# Deserializer.net
KiCad netlist of a schematic drawn in Altium Designer
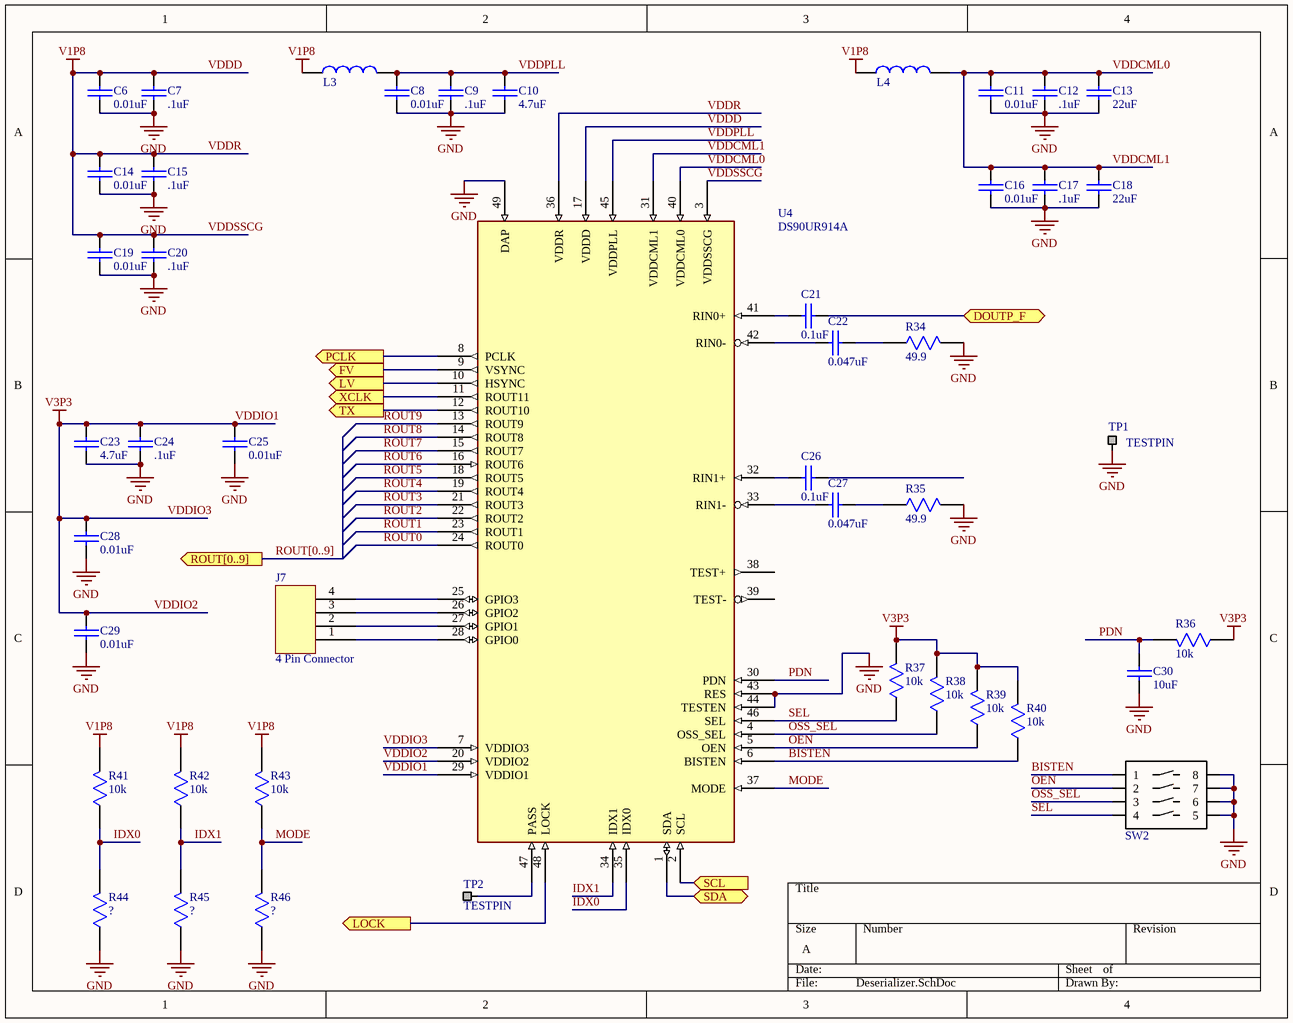
[diagram p0: Deserializer.SchDoc]

(export (version "E")
  (design (tool "Eeschema 10.0.6"))
  (components
    (comp (ref "C6")
      (value "0.01uF")
      (footprint "SMD Capacitor 0603")
      (libsource (lib "DA_Component_Library") (part "Capacitor"))
    )
    (comp (ref "C7")
      (value ".1uF")
      (footprint "SMD Capacitor 0603")
      (libsource (lib "DA_Component_Library") (part "Capacitor"))
    )
    (comp (ref "C8")
      (value "0.01uF")
      (footprint "SMD Capacitor 0603")
      (libsource (lib "DA_Component_Library") (part "Capacitor"))
    )
    (comp (ref "C9")
      (value ".1uF")
      (footprint "SMD Capacitor 0603")
      (libsource (lib "DA_Component_Library") (part "Capacitor"))
    )
    (comp (ref "C10")
      (value "4.7uF")
      (footprint "SMD Capacitor 0603")
      (libsource (lib "DA_Component_Library") (part "Capacitor"))
    )
    (comp (ref "C11")
      (value "0.01uF")
      (footprint "SMD Capacitor 0603")
      (libsource (lib "DA_Component_Library") (part "Capacitor"))
    )
    (comp (ref "C12")
      (value ".1uF")
      (footprint "SMD Capacitor 0603")
      (libsource (lib "DA_Component_Library") (part "Capacitor"))
    )
    (comp (ref "C13")
      (value "22uF")
      (footprint "SMD Capacitor 0603")
      (libsource (lib "DA_Component_Library") (part "Capacitor"))
    )
    (comp (ref "C14")
      (value "0.01uF")
      (footprint "SMD Capacitor 0603")
      (libsource (lib "DA_Component_Library") (part "Capacitor"))
    )
    (comp (ref "C15")
      (value ".1uF")
      (footprint "SMD Capacitor 0603")
      (libsource (lib "DA_Component_Library") (part "Capacitor"))
    )
    (comp (ref "C16")
      (value "0.01uF")
      (footprint "SMD Capacitor 0603")
      (libsource (lib "DA_Component_Library") (part "Capacitor"))
    )
    (comp (ref "C17")
      (value ".1uF")
      (footprint "SMD Capacitor 0603")
      (libsource (lib "DA_Component_Library") (part "Capacitor"))
    )
    (comp (ref "C18")
      (value "22uF")
      (footprint "SMD Capacitor 0603")
      (libsource (lib "DA_Component_Library") (part "Capacitor"))
    )
    (comp (ref "C19")
      (value "0.01uF")
      (footprint "SMD Capacitor 0603")
      (libsource (lib "DA_Component_Library") (part "Capacitor"))
    )
    (comp (ref "C20")
      (value ".1uF")
      (footprint "SMD Capacitor 0603")
      (libsource (lib "DA_Component_Library") (part "Capacitor"))
    )
    (comp (ref "C21")
      (value "0.1uF")
      (footprint "SMD CAP 0402")
      (libsource (lib "DA_Component_Library") (part "Capacitor"))
    )
    (comp (ref "C22")
      (value "0.047uF")
      (footprint "SMD CAP 0402")
      (libsource (lib "DA_Component_Library") (part "Capacitor"))
    )
    (comp (ref "C23")
      (value "4.7uF")
      (footprint "SMD Capacitor 0603")
      (libsource (lib "DA_Component_Library") (part "Capacitor"))
    )
    (comp (ref "C24")
      (value ".1uF")
      (footprint "SMD Capacitor 0603")
      (libsource (lib "DA_Component_Library") (part "Capacitor"))
    )
    (comp (ref "C25")
      (value "0.01uF")
      (footprint "SMD Capacitor 0603")
      (libsource (lib "DA_Component_Library") (part "Capacitor"))
    )
    (comp (ref "C26")
      (value "0.1uF")
      (footprint "SMD CAP 0402")
      (libsource (lib "DA_Component_Library") (part "Capacitor"))
    )
    (comp (ref "C27")
      (value "0.047uF")
      (footprint "SMD CAP 0402")
      (libsource (lib "DA_Component_Library") (part "Capacitor"))
    )
    (comp (ref "C28")
      (value "0.01uF")
      (footprint "SMD Capacitor 0603")
      (libsource (lib "DA_Component_Library") (part "Capacitor"))
    )
    (comp (ref "C29")
      (value "0.01uF")
      (footprint "SMD Capacitor 0603")
      (libsource (lib "DA_Component_Library") (part "Capacitor"))
    )
    (comp (ref "C30")
      (value "10uF")
      (footprint "SMD Capacitor 0603")
      (libsource (lib "DA_Component_Library") (part "Capacitor"))
    )
    (comp (ref "J7")
      (value "4 Pin Connector")
      (footprint "4Pin Verital 0.1\"")
      (libsource (lib "DA_Component_Library") (part "4 Pin Connector"))
    )
    (comp (ref "L3")
      (value "Ferrite Bead")
      (footprint "BLM18KG601SN1D")
      (libsource (lib "DA_Component_Library") (part "Ferrite Bead"))
    )
    (comp (ref "L4")
      (value "Ferrite Bead")
      (footprint "BLM18KG601SN1D")
      (libsource (lib "DA_Component_Library") (part "Ferrite Bead"))
    )
    (comp (ref "R34")
      (value "49.9")
      (footprint "SMD RES 0402")
      (libsource (lib "DA_Component_Library") (part "Resistor"))
    )
    (comp (ref "R35")
      (value "49.9")
      (footprint "SMD RES 0402")
      (libsource (lib "DA_Component_Library") (part "Resistor"))
    )
    (comp (ref "R36")
      (value "10k")
      (footprint "SMD Resistor 0603")
      (libsource (lib "DA_Component_Library") (part "Resistor"))
    )
    (comp (ref "R37")
      (value "10k")
      (footprint "SMD Resistor 0603")
      (libsource (lib "DA_Component_Library") (part "Resistor"))
    )
    (comp (ref "R38")
      (value "10k")
      (footprint "SMD Resistor 0603")
      (libsource (lib "DA_Component_Library") (part "Resistor"))
    )
    (comp (ref "R39")
      (value "10k")
      (footprint "SMD Resistor 0603")
      (libsource (lib "DA_Component_Library") (part "Resistor"))
    )
    (comp (ref "R40")
      (value "10k")
      (footprint "SMD Resistor 0603")
      (libsource (lib "DA_Component_Library") (part "Resistor"))
    )
    (comp (ref "R41")
      (value "10k")
      (footprint "SMD Resistor 0603")
      (libsource (lib "DA_Component_Library") (part "Resistor"))
    )
    (comp (ref "R42")
      (value "10k")
      (footprint "SMD Resistor 0603")
      (libsource (lib "DA_Component_Library") (part "Resistor"))
    )
    (comp (ref "R43")
      (value "10k")
      (footprint "SMD Resistor 0603")
      (libsource (lib "DA_Component_Library") (part "Resistor"))
    )
    (comp (ref "R44")
      (value "?")
      (footprint "SMD Resistor 0603")
      (libsource (lib "DA_Component_Library") (part "Resistor"))
    )
    (comp (ref "R45")
      (value "?")
      (footprint "SMD Resistor 0603")
      (libsource (lib "DA_Component_Library") (part "Resistor"))
    )
    (comp (ref "R46")
      (value "?")
      (footprint "SMD Resistor 0603")
      (libsource (lib "DA_Component_Library") (part "Resistor"))
    )
    (comp (ref "SW2")
      (value "SW_DIP_4Position")
      (footprint "218-4LPST")
      (libsource (lib "DA_Component_Library") (part "SW_DIP_4Position"))
    )
    (comp (ref "TP1")
      (value "TESTPIN")
      (footprint "TESTPIN")
      (description "TESTPIN SINGLE PIN HEADER")
      (libsource (lib "vh_altium_library") (part "TESTPIN"))
    )
    (comp (ref "TP2")
      (value "TESTPIN")
      (footprint "TESTPIN")
      (description "TESTPIN SINGLE PIN HEADER")
      (libsource (lib "") (part "TESTPIN_1"))
    )
    (comp (ref "U4")
      (value "DS90UR914A")
      (footprint "WQFN48 for DS90UB914A")
      (libsource (lib "DA_Component_Library") (part "DS90UR914A"))
    )
  )
  (nets
    (net (code "1") (name "/BISTEN") (class "Default")
      (node (ref "R40") (pin "0") (pinfunction "0_0") (pintype "passive"))
      (node (ref "SW2") (pin "1") (pinfunction "1_1") (pintype "passive"))
      (node (ref "U4") (pin "6") (pinfunction "BISTEN_6") (pintype "input"))
    )
    (net (code "2") (name "/DOUTP_F") (class "Default")
      (node (ref "C21") (pin "1") (pinfunction "1_1") (pintype "passive"))
    )
    (net (code "3") (name "/FV") (class "Default")
      (node (ref "U4") (pin "9") (pinfunction "VSYNC_9") (pintype "output"))
    )
    (net (code "4") (name "/IDX0") (class "Default")
      (node (ref "R41") (pin "0") (pinfunction "0_0") (pintype "passive"))
      (node (ref "R44") (pin "1") (pinfunction "1_1") (pintype "passive"))
      (node (ref "U4") (pin "35") (pinfunction "IDX0_35") (pintype "input"))
    )
    (net (code "5") (name "/IDX1") (class "Default")
      (node (ref "R42") (pin "0") (pinfunction "0_0") (pintype "passive"))
      (node (ref "R45") (pin "1") (pinfunction "1_1") (pintype "passive"))
      (node (ref "U4") (pin "34") (pinfunction "IDX1_34") (pintype "input"))
    )
    (net (code "6") (name "/LOCK") (class "Default")
      (node (ref "U4") (pin "48") (pinfunction "LOCK_48") (pintype "input"))
    )
    (net (code "7") (name "/LV") (class "Default")
      (node (ref "U4") (pin "10") (pinfunction "HSYNC_10") (pintype "output"))
    )
    (net (code "8") (name "/MODE") (class "Default")
      (node (ref "R43") (pin "0") (pinfunction "0_0") (pintype "passive"))
      (node (ref "R46") (pin "1") (pinfunction "1_1") (pintype "passive"))
      (node (ref "U4") (pin "37") (pinfunction "MODE_37") (pintype "input"))
    )
    (net (code "9") (name "/OEN") (class "Default")
      (node (ref "R39") (pin "0") (pinfunction "0_0") (pintype "passive"))
      (node (ref "SW2") (pin "2") (pinfunction "2_2") (pintype "passive"))
      (node (ref "U4") (pin "5") (pinfunction "OEN_5") (pintype "input"))
    )
    (net (code "10") (name "/OSS_SEL") (class "Default")
      (node (ref "R38") (pin "0") (pinfunction "0_0") (pintype "passive"))
      (node (ref "SW2") (pin "3") (pinfunction "3_3") (pintype "passive"))
      (node (ref "U4") (pin "4") (pinfunction "OSS_SEL_4") (pintype "input"))
    )
    (net (code "11") (name "/PCLK") (class "Default")
      (node (ref "U4") (pin "8") (pinfunction "PCLK_8") (pintype "output"))
    )
    (net (code "12") (name "/PDN") (class "Default")
      (node (ref "C30") (pin "0") (pinfunction "0_0") (pintype "passive"))
      (node (ref "R36") (pin "1") (pinfunction "1_1") (pintype "passive"))
      (node (ref "U4") (pin "30") (pinfunction "PDN_30") (pintype "input"))
    )
    (net (code "13") (name "/ROUT0") (class "Default")
      (node (ref "U4") (pin "24") (pinfunction "ROUT0_24") (pintype "output"))
    )
    (net (code "14") (name "/ROUT1") (class "Default")
      (node (ref "U4") (pin "23") (pinfunction "ROUT1_23") (pintype "output"))
    )
    (net (code "15") (name "/ROUT2") (class "Default")
      (node (ref "U4") (pin "22") (pinfunction "ROUT2_22") (pintype "output"))
    )
    (net (code "16") (name "/ROUT3") (class "Default")
      (node (ref "U4") (pin "21") (pinfunction "ROUT3_21") (pintype "output"))
    )
    (net (code "17") (name "/ROUT4") (class "Default")
      (node (ref "U4") (pin "19") (pinfunction "ROUT4_19") (pintype "output"))
    )
    (net (code "18") (name "/ROUT5") (class "Default")
      (node (ref "U4") (pin "18") (pinfunction "ROUT5_18") (pintype "output"))
    )
    (net (code "19") (name "/ROUT6") (class "Default")
      (node (ref "U4") (pin "16") (pinfunction "ROUT6_16") (pintype "input"))
    )
    (net (code "20") (name "/ROUT7") (class "Default")
      (node (ref "U4") (pin "15") (pinfunction "ROUT7_15") (pintype "output"))
    )
    (net (code "21") (name "/ROUT8") (class "Default")
      (node (ref "U4") (pin "14") (pinfunction "ROUT8_14") (pintype "output"))
    )
    (net (code "22") (name "/ROUT9") (class "Default")
      (node (ref "U4") (pin "13") (pinfunction "ROUT9_13") (pintype "output"))
    )
    (net (code "24") (name "/SCL") (class "Default")
      (node (ref "U4") (pin "2") (pinfunction "SCL_2") (pintype "input"))
    )
    (net (code "25") (name "/SDA") (class "Default")
      (node (ref "U4") (pin "1") (pinfunction "SDA_1") (pintype "bidirectional"))
    )
    (net (code "26") (name "/SEL") (class "Default")
      (node (ref "R37") (pin "0") (pinfunction "0_0") (pintype "passive"))
      (node (ref "SW2") (pin "4") (pinfunction "4_4") (pintype "passive"))
      (node (ref "U4") (pin "46") (pinfunction "SEL_46") (pintype "input"))
    )
    (net (code "27") (name "/TX") (class "Default")
      (node (ref "U4") (pin "12") (pinfunction "ROUT10_12") (pintype "output"))
    )
    (net (code "28") (name "/VDDCML0") (class "Default")
      (node (ref "C11") (pin "0") (pinfunction "0_0") (pintype "passive"))
      (node (ref "C12") (pin "0") (pinfunction "0_0") (pintype "passive"))
      (node (ref "C13") (pin "0") (pinfunction "0_0") (pintype "passive"))
      (node (ref "C16") (pin "0") (pinfunction "0_0") (pintype "passive"))
      (node (ref "C17") (pin "0") (pinfunction "0_0") (pintype "passive"))
      (node (ref "C18") (pin "0") (pinfunction "0_0") (pintype "passive"))
      (node (ref "L4") (pin "2") (pinfunction "2_2") (pintype "passive"))
      (node (ref "U4") (pin "31") (pinfunction "VDDCML1_31") (pintype "input"))
      (node (ref "U4") (pin "40") (pinfunction "VDDCML0_40") (pintype "input"))
    )
    (net (code "29") (name "/VDDPLL") (class "Default")
      (node (ref "C10") (pin "0") (pinfunction "0_0") (pintype "passive"))
      (node (ref "C8") (pin "0") (pinfunction "0_0") (pintype "passive"))
      (node (ref "C9") (pin "0") (pinfunction "0_0") (pintype "passive"))
      (node (ref "L3") (pin "2") (pinfunction "2_2") (pintype "passive"))
      (node (ref "U4") (pin "45") (pinfunction "VDDPLL_45") (pintype "input"))
    )
    (net (code "30") (name "/XCLK") (class "Default")
      (node (ref "U4") (pin "11") (pinfunction "ROUT11_11") (pintype "output"))
    )
    (net (code "31") (name "GND") (class "Default")
      (node (ref "C10") (pin "1") (pinfunction "1_1") (pintype "passive"))
      (node (ref "C11") (pin "1") (pinfunction "1_1") (pintype "passive"))
      (node (ref "C12") (pin "1") (pinfunction "1_1") (pintype "passive"))
      (node (ref "C13") (pin "1") (pinfunction "1_1") (pintype "passive"))
      (node (ref "C14") (pin "1") (pinfunction "1_1") (pintype "passive"))
      (node (ref "C15") (pin "1") (pinfunction "1_1") (pintype "passive"))
      (node (ref "C16") (pin "1") (pinfunction "1_1") (pintype "passive"))
      (node (ref "C17") (pin "1") (pinfunction "1_1") (pintype "passive"))
      (node (ref "C18") (pin "1") (pinfunction "1_1") (pintype "passive"))
      (node (ref "C19") (pin "1") (pinfunction "1_1") (pintype "passive"))
      (node (ref "C20") (pin "1") (pinfunction "1_1") (pintype "passive"))
      (node (ref "C23") (pin "1") (pinfunction "1_1") (pintype "passive"))
      (node (ref "C24") (pin "1") (pinfunction "1_1") (pintype "passive"))
      (node (ref "C25") (pin "1") (pinfunction "1_1") (pintype "passive"))
      (node (ref "C28") (pin "1") (pinfunction "1_1") (pintype "passive"))
      (node (ref "C29") (pin "1") (pinfunction "1_1") (pintype "passive"))
      (node (ref "C30") (pin "1") (pinfunction "1_1") (pintype "passive"))
      (node (ref "C6") (pin "1") (pinfunction "1_1") (pintype "passive"))
      (node (ref "C7") (pin "1") (pinfunction "1_1") (pintype "passive"))
      (node (ref "C8") (pin "1") (pinfunction "1_1") (pintype "passive"))
      (node (ref "C9") (pin "1") (pinfunction "1_1") (pintype "passive"))
      (node (ref "R34") (pin "1") (pinfunction "1_1") (pintype "passive"))
      (node (ref "R35") (pin "1") (pinfunction "1_1") (pintype "passive"))
      (node (ref "R44") (pin "0") (pinfunction "0_0") (pintype "passive"))
      (node (ref "R45") (pin "0") (pinfunction "0_0") (pintype "passive"))
      (node (ref "R46") (pin "0") (pinfunction "0_0") (pintype "passive"))
      (node (ref "SW2") (pin "5") (pinfunction "5_5") (pintype "passive"))
      (node (ref "SW2") (pin "6") (pinfunction "6_6") (pintype "passive"))
      (node (ref "SW2") (pin "7") (pinfunction "7_7") (pintype "passive"))
      (node (ref "SW2") (pin "8") (pinfunction "8_8") (pintype "passive"))
      (node (ref "TP1") (pin "1") (pinfunction "1_1") (pintype "passive"))
      (node (ref "U4") (pin "43") (pinfunction "RES_43") (pintype "input"))
      (node (ref "U4") (pin "44") (pinfunction "TESTEN_44") (pintype "input"))
      (node (ref "U4") (pin "49") (pinfunction "DAP_49") (pintype "input"))
    )
    (net (code "32") (name "Net-(C22-Pad1)") (class "Default")
      (node (ref "C22") (pin "1") (pinfunction "1_1") (pintype "passive"))
      (node (ref "R34") (pin "0") (pinfunction "0_0") (pintype "passive"))
    )
    (net (code "33") (name "Net-(C27-Pad1)") (class "Default")
      (node (ref "C27") (pin "1") (pinfunction "1_1") (pintype "passive"))
      (node (ref "R35") (pin "0") (pinfunction "0_0") (pintype "passive"))
    )
    (net (code "34") (name "Net-(U4-GPIO0)") (class "Default")
      (node (ref "J7") (pin "1") (pinfunction "1_1") (pintype "passive"))
      (node (ref "U4") (pin "28") (pinfunction "GPIO0_28") (pintype "bidirectional"))
    )
    (net (code "35") (name "Net-(U4-GPIO1)") (class "Default")
      (node (ref "J7") (pin "2") (pinfunction "2_2") (pintype "passive"))
      (node (ref "U4") (pin "27") (pinfunction "GPIO1_27") (pintype "bidirectional"))
    )
    (net (code "36") (name "Net-(U4-GPIO2)") (class "Default")
      (node (ref "J7") (pin "3") (pinfunction "3_3") (pintype "passive"))
      (node (ref "U4") (pin "26") (pinfunction "GPIO2_26") (pintype "bidirectional"))
    )
    (net (code "37") (name "Net-(U4-GPIO3)") (class "Default")
      (node (ref "J7") (pin "4") (pinfunction "4_4") (pintype "passive"))
      (node (ref "U4") (pin "25") (pinfunction "GPIO3_25") (pintype "bidirectional"))
    )
    (net (code "38") (name "Net-(U4-PASS)") (class "Default")
      (node (ref "TP2") (pin "1") (pinfunction "1_1") (pintype "passive"))
      (node (ref "U4") (pin "47") (pinfunction "PASS_47") (pintype "input"))
    )
    (net (code "39") (name "Net-(U4-RIN0+)") (class "Default")
      (node (ref "C21") (pin "0") (pinfunction "0_0") (pintype "passive"))
      (node (ref "U4") (pin "41") (pinfunction "RIN0+_41") (pintype "input"))
    )
    (net (code "40") (name "Net-(U4-RIN0-)") (class "Default")
      (node (ref "C22") (pin "0") (pinfunction "0_0") (pintype "passive"))
      (node (ref "U4") (pin "42") (pinfunction "RIN0-_42") (pintype "input"))
    )
    (net (code "41") (name "Net-(U4-RIN1+)") (class "Default")
      (node (ref "C26") (pin "0") (pinfunction "0_0") (pintype "passive"))
      (node (ref "U4") (pin "32") (pinfunction "RIN1+_32") (pintype "input"))
    )
    (net (code "42") (name "Net-(U4-RIN1-)") (class "Default")
      (node (ref "C27") (pin "0") (pinfunction "0_0") (pintype "passive"))
      (node (ref "U4") (pin "33") (pinfunction "RIN1-_33") (pintype "input"))
    )
    (net (code "43") (name "V1P8") (class "Default")
      (node (ref "C14") (pin "0") (pinfunction "0_0") (pintype "passive"))
      (node (ref "C15") (pin "0") (pinfunction "0_0") (pintype "passive"))
      (node (ref "C19") (pin "0") (pinfunction "0_0") (pintype "passive"))
      (node (ref "C20") (pin "0") (pinfunction "0_0") (pintype "passive"))
      (node (ref "C6") (pin "0") (pinfunction "0_0") (pintype "passive"))
      (node (ref "C7") (pin "0") (pinfunction "0_0") (pintype "passive"))
      (node (ref "L3") (pin "1") (pinfunction "1_1") (pintype "passive"))
      (node (ref "L4") (pin "1") (pinfunction "1_1") (pintype "passive"))
      (node (ref "R41") (pin "1") (pinfunction "1_1") (pintype "passive"))
      (node (ref "R42") (pin "1") (pinfunction "1_1") (pintype "passive"))
      (node (ref "R43") (pin "1") (pinfunction "1_1") (pintype "passive"))
      (node (ref "U4") (pin "17") (pinfunction "VDDD_17") (pintype "input"))
      (node (ref "U4") (pin "3") (pinfunction "VDDSSCG_3") (pintype "input"))
      (node (ref "U4") (pin "36") (pinfunction "VDDR_36") (pintype "input"))
    )
    (net (code "44") (name "V3P3") (class "Default")
      (node (ref "C23") (pin "0") (pinfunction "0_0") (pintype "passive"))
      (node (ref "C24") (pin "0") (pinfunction "0_0") (pintype "passive"))
      (node (ref "C25") (pin "0") (pinfunction "0_0") (pintype "passive"))
      (node (ref "C28") (pin "0") (pinfunction "0_0") (pintype "passive"))
      (node (ref "C29") (pin "0") (pinfunction "0_0") (pintype "passive"))
      (node (ref "R36") (pin "0") (pinfunction "0_0") (pintype "passive"))
      (node (ref "R37") (pin "1") (pinfunction "1_1") (pintype "passive"))
      (node (ref "R38") (pin "1") (pinfunction "1_1") (pintype "passive"))
      (node (ref "R39") (pin "1") (pinfunction "1_1") (pintype "passive"))
      (node (ref "R40") (pin "1") (pinfunction "1_1") (pintype "passive"))
      (node (ref "U4") (pin "20") (pinfunction "VDDIO2_20") (pintype "input"))
      (node (ref "U4") (pin "29") (pinfunction "VDDIO1_29") (pintype "input"))
      (node (ref "U4") (pin "7") (pinfunction "VDDIO3_7") (pintype "input"))
    )
    (net (code "45") (name "unconnected-(C26-Pad1)") (class "Default")
      (node (ref "C26") (pin "1") (pinfunction "1_1") (pintype "passive"))
    )
    (net (code "46") (name "unconnected-(U4-TEST+-Pad38)") (class "Default")
      (node (ref "U4") (pin "38") (pinfunction "TEST+_38") (pintype "output"))
    )
    (net (code "47") (name "unconnected-(U4-TEST--Pad39)") (class "Default")
      (node (ref "U4") (pin "39") (pinfunction "TEST-_39") (pintype "output"))
    )
  )
)
